# 09_EMMC.net
KiCad netlist of a schematic drawn in Altium Designer
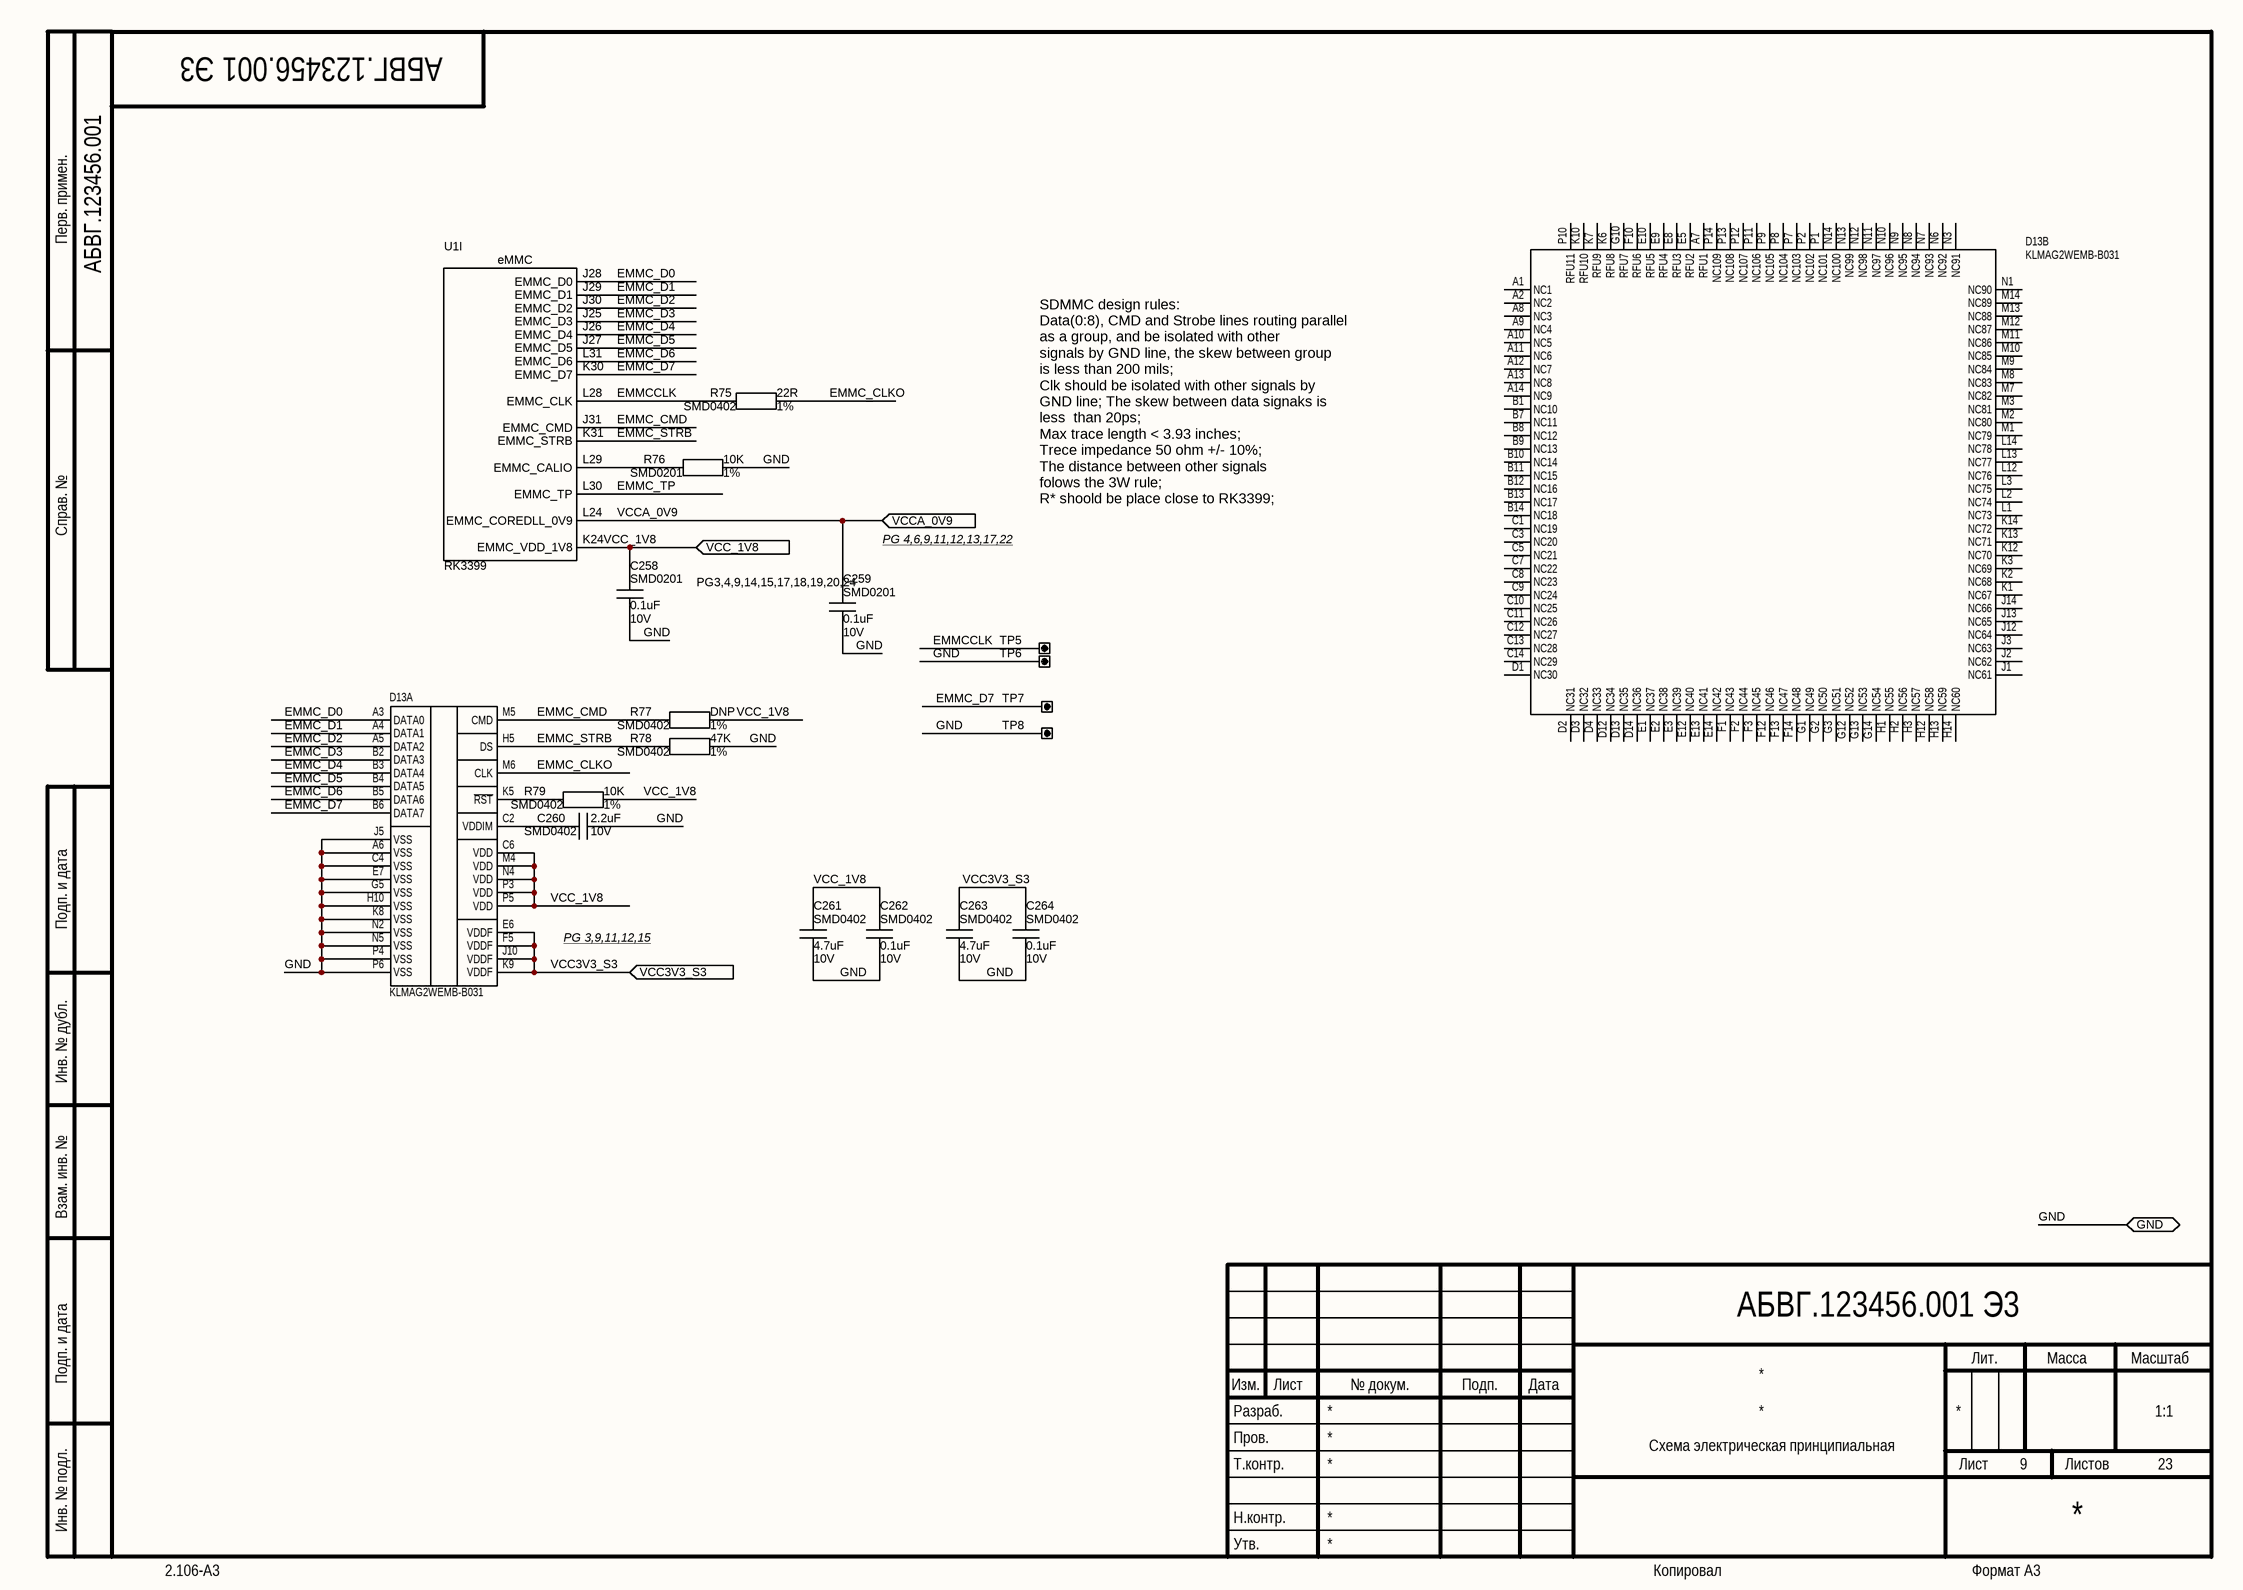
[diagram p0: 09 EMMC.SchDoc]

(export (version "E")
  (design (tool "Eeschema 10.0.6"))
  (components
    (comp (ref "C258")
      (value "0.1uF")
      (footprint "Didur_PcbLib_1:CAP_SMD_0201")
      (fields
        (field (name "PACKAGE") "SMD0201")
        (field (name "PARTNUMBER") "CC0201KRX5R6BB104")
        (field (name "VOLTAGE") "10V")
      )
      (libsource (lib "Didur_SchLib_1") (part "Ceramic_Cap"))
    )
    (comp (ref "C259")
      (value "0.1uF")
      (footprint "Didur_PcbLib_1:CAP_SMD_0201")
      (fields
        (field (name "PACKAGE") "SMD0201")
        (field (name "PARTNUMBER") "CC0201KRX5R6BB104")
        (field (name "VOLTAGE") "10V")
      )
      (libsource (lib "Didur_SchLib_1") (part "Ceramic_Cap"))
    )
    (comp (ref "C260")
      (value "2.2uF")
      (footprint "Didur_PcbLib_1:CAP_SMD_0402")
      (fields
        (field (name "PACKAGE") "SMD0402")
        (field (name "PARTNUMBER") "CC0402KRX5R6BB225")
        (field (name "VOLTAGE") "10V")
      )
      (libsource (lib "Didur_SchLib_1") (part "Ceramic_Cap"))
    )
    (comp (ref "C261")
      (value "4.7uF")
      (footprint "Didur_PcbLib_1:CAP_SMD_0402")
      (fields
        (field (name "PACKAGE") "SMD0402")
        (field (name "PARTNUMBER") "CL05A475KP5NRNC")
        (field (name "VOLTAGE") "10V")
      )
      (libsource (lib "Didur_SchLib_1") (part "Ceramic_Cap"))
    )
    (comp (ref "C262")
      (value "0.1uF")
      (footprint "Didur_PcbLib_1:CAP_SMD_0402")
      (fields
        (field (name "PACKAGE") "SMD0402")
        (field (name "PARTNUMBER") "CC0402KRX5R6BB104")
        (field (name "VOLTAGE") "10V")
      )
      (libsource (lib "Didur_SchLib_1") (part "Ceramic_Cap"))
    )
    (comp (ref "C263")
      (value "4.7uF")
      (footprint "Didur_PcbLib_1:CAP_SMD_0402")
      (fields
        (field (name "PACKAGE") "SMD0402")
        (field (name "PARTNUMBER") "CL05A475KP5NRNC")
        (field (name "VOLTAGE") "10V")
      )
      (libsource (lib "Didur_SchLib_1") (part "Ceramic_Cap"))
    )
    (comp (ref "C264")
      (value "0.1uF")
      (footprint "Didur_PcbLib_1:CAP_SMD_0402")
      (fields
        (field (name "PACKAGE") "SMD0402")
        (field (name "PARTNUMBER") "CC0402KRX5R6BB104")
        (field (name "VOLTAGE") "10V")
      )
      (libsource (lib "Didur_SchLib_1") (part "Ceramic_Cap"))
    )
    (comp (ref "D13")
      (value "KLMAG2WEMB-B031")
      (footprint "Didur_PcbLib_1:FBGA153")
      (libsource (lib "Didur_SchLib_1") (part "KLMAG2WEMB-B031"))
    )
    (comp (ref "R75")
      (value "22R")
      (footprint "Didur_PcbLib_1:RES_SMD_0402_SMALL")
      (fields
        (field (name "PACKAGE") "SMD0402")
        (field (name "PARTNUMBER") "RC0402FR-0722RL")
        (field (name "TOLERANCE") "1%")
      )
      (libsource (lib "") (part "Chip_Res_1"))
    )
    (comp (ref "R76")
      (value "10K")
      (footprint "Didur_PcbLib_1:RES_SMD_0201")
      (fields
        (field (name "PACKAGE") "SMD0201")
        (field (name "PARTNUMBER") "RC0201FR-0710KL")
        (field (name "TOLERANCE") "1%")
      )
      (libsource (lib "Didur_SchLib_1") (part "Chip_Res"))
    )
    (comp (ref "R77")
      (value "DNP")
      (footprint "Didur_PcbLib_1:RES_SMD_0402")
      (fields
        (field (name "PACKAGE") "SMD0402")
        (field (name "PARTNUMBER") "Do Not Place")
        (field (name "TOLERANCE") "1%")
      )
      (libsource (lib "") (part "Chip_Res_2"))
    )
    (comp (ref "R78")
      (value "47K")
      (footprint "Didur_PcbLib_1:RES_SMD_0402")
      (fields
        (field (name "PACKAGE") "SMD0402")
        (field (name "PARTNUMBER") "RC0402FR-1347KL")
        (field (name "TOLERANCE") "1%")
      )
      (libsource (lib "") (part "Chip_Res_1"))
    )
    (comp (ref "R79")
      (value "10K")
      (footprint "Didur_PcbLib_1:RES_SMD_0402")
      (fields
        (field (name "PACKAGE") "SMD0402")
        (field (name "PARTNUMBER") "RC0402FR-0710KL")
        (field (name "TOLERANCE") "1%")
      )
      (libsource (lib "Didur_SchLib_1") (part "Chip_Res"))
    )
    (comp (ref "TP5")
      (value "TEST POINT SMD 1MM")
      (footprint "Didur_PcbLib_1:TEST POINT SMD 1MM")
      (libsource (lib "Didur_SchLib_1") (part "TP"))
    )
    (comp (ref "TP6")
      (value "TEST POINT SMD 1MM")
      (footprint "Didur_PcbLib_1:TEST POINT SMD 1MM")
      (libsource (lib "Didur_SchLib_1") (part "TP"))
    )
    (comp (ref "TP7")
      (value "TEST POINT SMD 1MM")
      (footprint "Didur_PcbLib_1:TEST POINT SMD 1MM")
      (libsource (lib "Didur_SchLib_1") (part "TP"))
    )
    (comp (ref "TP8")
      (value "TEST POINT SMD 1MM")
      (footprint "Didur_PcbLib_1:TEST POINT SMD 1MM")
      (libsource (lib "Didur_SchLib_1") (part "TP"))
    )
    (comp (ref "U1")
      (value "RK3399")
      (footprint "BGA828C65P31X31_2100X2100X161N")
      (fields (field (name "Comment") "RK3399_FF"))
      (libsource (lib "Didur_SchLib_1") (part "RK3399_FF"))
    )
  )
  (nets
    (net (code "1") (name "/EMMCCLK") (class "Default")
      (node (ref "R75") (pin "2") (pinfunction "2_2") (pintype "passive"))
      (node (ref "TP5") (pin "1") (pinfunction "1_1") (pintype "passive"))
      (node (ref "U1") (pin "L28") (pinfunction "EMMC_CLK_L28") (pintype "passive"))
    )
    (net (code "2") (name "/EMMC_CLKO") (class "Default")
      (node (ref "D13") (pin "M6") (pinfunction "CLK_M6") (pintype "passive"))
      (node (ref "R75") (pin "1") (pinfunction "1_1") (pintype "passive"))
    )
    (net (code "3") (name "/EMMC_CMD") (class "Default")
      (node (ref "D13") (pin "M5") (pinfunction "CMD_M5") (pintype "passive"))
      (node (ref "R77") (pin "1") (pinfunction "1_1") (pintype "passive"))
      (node (ref "U1") (pin "J31") (pinfunction "EMMC_CMD_J31") (pintype "passive"))
    )
    (net (code "4") (name "/EMMC_D0") (class "Default")
      (node (ref "D13") (pin "A3") (pinfunction "DATA0_A3") (pintype "passive"))
      (node (ref "U1") (pin "J28") (pinfunction "EMMC_D0_J28") (pintype "passive"))
    )
    (net (code "5") (name "/EMMC_D1") (class "Default")
      (node (ref "D13") (pin "A4") (pinfunction "DATA1_A4") (pintype "passive"))
      (node (ref "U1") (pin "J29") (pinfunction "EMMC_D1_J29") (pintype "passive"))
    )
    (net (code "6") (name "/EMMC_D2") (class "Default")
      (node (ref "D13") (pin "A5") (pinfunction "DATA2_A5") (pintype "passive"))
      (node (ref "U1") (pin "J30") (pinfunction "EMMC_D2_J30") (pintype "passive"))
    )
    (net (code "7") (name "/EMMC_D3") (class "Default")
      (node (ref "D13") (pin "B2") (pinfunction "DATA3_B2") (pintype "passive"))
      (node (ref "U1") (pin "J25") (pinfunction "EMMC_D3_J25") (pintype "passive"))
    )
    (net (code "8") (name "/EMMC_D4") (class "Default")
      (node (ref "D13") (pin "B3") (pinfunction "DATA4_B3") (pintype "passive"))
      (node (ref "U1") (pin "J26") (pinfunction "EMMC_D4_J26") (pintype "passive"))
    )
    (net (code "9") (name "/EMMC_D5") (class "Default")
      (node (ref "D13") (pin "B4") (pinfunction "DATA5_B4") (pintype "passive"))
      (node (ref "U1") (pin "J27") (pinfunction "EMMC_D5_J27") (pintype "passive"))
    )
    (net (code "10") (name "/EMMC_D6") (class "Default")
      (node (ref "D13") (pin "B5") (pinfunction "DATA6_B5") (pintype "passive"))
      (node (ref "U1") (pin "L31") (pinfunction "EMMC_D6_L31") (pintype "passive"))
    )
    (net (code "11") (name "/EMMC_D7") (class "Default")
      (node (ref "D13") (pin "B6") (pinfunction "DATA7_B6") (pintype "passive"))
      (node (ref "TP7") (pin "1") (pinfunction "1_1") (pintype "passive"))
      (node (ref "U1") (pin "K30") (pinfunction "EMMC_D7_K30") (pintype "passive"))
    )
    (net (code "12") (name "/EMMC_STRB") (class "Default")
      (node (ref "D13") (pin "H5") (pinfunction "DS_H5") (pintype "passive"))
      (node (ref "R78") (pin "2") (pinfunction "2_2") (pintype "passive"))
      (node (ref "U1") (pin "K31") (pinfunction "EMMC_STRB_K31") (pintype "passive"))
    )
    (net (code "13") (name "/EMMC_TP") (class "Default")
      (node (ref "U1") (pin "L30") (pinfunction "EMMC_TP_L30") (pintype "passive"))
    )
    (net (code "14") (name "/GND") (class "Default")
      (node (ref "C258") (pin "2") (pinfunction "2_2") (pintype "power_in"))
      (node (ref "C259") (pin "2") (pinfunction "2_2") (pintype "power_in"))
      (node (ref "C260") (pin "2") (pinfunction "2_2") (pintype "power_in"))
      (node (ref "C261") (pin "1") (pinfunction "1_1") (pintype "power_in"))
      (node (ref "C262") (pin "2") (pinfunction "2_2") (pintype "power_in"))
      (node (ref "C263") (pin "1") (pinfunction "1_1") (pintype "power_in"))
      (node (ref "C264") (pin "2") (pinfunction "2_2") (pintype "power_in"))
      (node (ref "D13") (pin "A6") (pinfunction "VSS_A6") (pintype "passive"))
      (node (ref "D13") (pin "C4") (pinfunction "VSS_C4") (pintype "passive"))
      (node (ref "D13") (pin "E7") (pinfunction "VSS_E7") (pintype "passive"))
      (node (ref "D13") (pin "G5") (pinfunction "VSS_G5") (pintype "passive"))
      (node (ref "D13") (pin "H10") (pinfunction "VSS_H10") (pintype "passive"))
      (node (ref "D13") (pin "J5") (pinfunction "VSS_J5") (pintype "passive"))
      (node (ref "D13") (pin "K8") (pinfunction "VSS_K8") (pintype "passive"))
      (node (ref "D13") (pin "N2") (pinfunction "VSS_N2") (pintype "passive"))
      (node (ref "D13") (pin "N5") (pinfunction "VSS_N5") (pintype "passive"))
      (node (ref "D13") (pin "P4") (pinfunction "VSS_P4") (pintype "passive"))
      (node (ref "D13") (pin "P6") (pinfunction "VSS_P6") (pintype "passive"))
      (node (ref "R76") (pin "1") (pinfunction "1_1") (pintype "passive"))
      (node (ref "R78") (pin "1") (pinfunction "1_1") (pintype "passive"))
      (node (ref "TP6") (pin "1") (pinfunction "1_1") (pintype "passive"))
      (node (ref "TP8") (pin "1") (pinfunction "1_1") (pintype "passive"))
    )
    (net (code "15") (name "/VCC3V3_S3") (class "Default")
      (node (ref "C263") (pin "2") (pinfunction "2_2") (pintype "power_in"))
      (node (ref "C264") (pin "1") (pinfunction "1_1") (pintype "power_in"))
      (node (ref "D13") (pin "E6") (pinfunction "VDDF_E6") (pintype "passive"))
      (node (ref "D13") (pin "F5") (pinfunction "VDDF_F5") (pintype "passive"))
      (node (ref "D13") (pin "J10") (pinfunction "VDDF_J10") (pintype "passive"))
      (node (ref "D13") (pin "K9") (pinfunction "VDDF_K9") (pintype "passive"))
    )
    (net (code "16") (name "/VCCA_0V9") (class "Default")
      (node (ref "C259") (pin "1") (pinfunction "1_1") (pintype "power_in"))
      (node (ref "U1") (pin "L24") (pinfunction "EMMC_COREDLL_0V9_L24") (pintype "passive"))
    )
    (net (code "17") (name "/VCC_1V8") (class "Default")
      (node (ref "C258") (pin "1") (pinfunction "1_1") (pintype "power_in"))
      (node (ref "C261") (pin "2") (pinfunction "2_2") (pintype "power_in"))
      (node (ref "C262") (pin "1") (pinfunction "1_1") (pintype "power_in"))
      (node (ref "D13") (pin "C6") (pinfunction "VDD_C6") (pintype "passive"))
      (node (ref "D13") (pin "M4") (pinfunction "VDD_M4") (pintype "passive"))
      (node (ref "D13") (pin "N4") (pinfunction "VDD_N4") (pintype "passive"))
      (node (ref "D13") (pin "P3") (pinfunction "VDD_P3") (pintype "passive"))
      (node (ref "D13") (pin "P5") (pinfunction "VDD_P5") (pintype "passive"))
      (node (ref "R77") (pin "2") (pinfunction "2_2") (pintype "passive"))
      (node (ref "R79") (pin "1") (pinfunction "1_1") (pintype "passive"))
      (node (ref "U1") (pin "K24") (pinfunction "EMMC_VDD_1V8_K24") (pintype "passive"))
    )
    (net (code "18") (name "Net-(D13A-VDDIM)") (class "Default")
      (node (ref "C260") (pin "1") (pinfunction "1_1") (pintype "power_in"))
      (node (ref "D13") (pin "C2") (pinfunction "VDDIM_C2") (pintype "passive"))
    )
    (net (code "19") (name "Net-(D13A-~{RST})") (class "Default")
      (node (ref "D13") (pin "K5") (pinfunction "~{RST}_K5") (pintype "passive"))
      (node (ref "R79") (pin "2") (pinfunction "2_2") (pintype "passive"))
    )
    (net (code "20") (name "Net-(U1I-EMMC_CALIO)") (class "Default")
      (node (ref "R76") (pin "2") (pinfunction "2_2") (pintype "passive"))
      (node (ref "U1") (pin "L29") (pinfunction "EMMC_CALIO_L29") (pintype "passive"))
    )
    (net (code "21") (name "unconnected-(D13B-NC1-PadA1)") (class "Default")
      (node (ref "D13") (pin "A1") (pinfunction "NC1_A1") (pintype "passive"))
    )
    (net (code "22") (name "unconnected-(D13B-NC2-PadA2)") (class "Default")
      (node (ref "D13") (pin "A2") (pinfunction "NC2_A2") (pintype "passive"))
    )
    (net (code "23") (name "unconnected-(D13B-NC3-PadA8)") (class "Default")
      (node (ref "D13") (pin "A8") (pinfunction "NC3_A8") (pintype "passive"))
    )
    (net (code "24") (name "unconnected-(D13B-NC4-PadA9)") (class "Default")
      (node (ref "D13") (pin "A9") (pinfunction "NC4_A9") (pintype "passive"))
    )
    (net (code "25") (name "unconnected-(D13B-NC5-PadA10)") (class "Default")
      (node (ref "D13") (pin "A10") (pinfunction "NC5_A10") (pintype "passive"))
    )
    (net (code "26") (name "unconnected-(D13B-NC6-PadA11)") (class "Default")
      (node (ref "D13") (pin "A11") (pinfunction "NC6_A11") (pintype "passive"))
    )
    (net (code "27") (name "unconnected-(D13B-NC7-PadA12)") (class "Default")
      (node (ref "D13") (pin "A12") (pinfunction "NC7_A12") (pintype "passive"))
    )
    (net (code "28") (name "unconnected-(D13B-NC8-PadA13)") (class "Default")
      (node (ref "D13") (pin "A13") (pinfunction "NC8_A13") (pintype "passive"))
    )
    (net (code "29") (name "unconnected-(D13B-NC9-PadA14)") (class "Default")
      (node (ref "D13") (pin "A14") (pinfunction "NC9_A14") (pintype "passive"))
    )
    (net (code "30") (name "unconnected-(D13B-NC10-PadB1)") (class "Default")
      (node (ref "D13") (pin "B1") (pinfunction "NC10_B1") (pintype "passive"))
    )
    (net (code "31") (name "unconnected-(D13B-NC11-PadB7)") (class "Default")
      (node (ref "D13") (pin "B7") (pinfunction "NC11_B7") (pintype "passive"))
    )
    (net (code "32") (name "unconnected-(D13B-NC12-PadB8)") (class "Default")
      (node (ref "D13") (pin "B8") (pinfunction "NC12_B8") (pintype "passive"))
    )
    (net (code "33") (name "unconnected-(D13B-NC13-PadB9)") (class "Default")
      (node (ref "D13") (pin "B9") (pinfunction "NC13_B9") (pintype "passive"))
    )
    (net (code "34") (name "unconnected-(D13B-NC14-PadB10)") (class "Default")
      (node (ref "D13") (pin "B10") (pinfunction "NC14_B10") (pintype "passive"))
    )
    (net (code "35") (name "unconnected-(D13B-NC15-PadB11)") (class "Default")
      (node (ref "D13") (pin "B11") (pinfunction "NC15_B11") (pintype "passive"))
    )
    (net (code "36") (name "unconnected-(D13B-NC16-PadB12)") (class "Default")
      (node (ref "D13") (pin "B12") (pinfunction "NC16_B12") (pintype "passive"))
    )
    (net (code "37") (name "unconnected-(D13B-NC17-PadB13)") (class "Default")
      (node (ref "D13") (pin "B13") (pinfunction "NC17_B13") (pintype "passive"))
    )
    (net (code "38") (name "unconnected-(D13B-NC18-PadB14)") (class "Default")
      (node (ref "D13") (pin "B14") (pinfunction "NC18_B14") (pintype "passive"))
    )
    (net (code "39") (name "unconnected-(D13B-NC19-PadC1)") (class "Default")
      (node (ref "D13") (pin "C1") (pinfunction "NC19_C1") (pintype "passive"))
    )
    (net (code "40") (name "unconnected-(D13B-NC20-PadC3)") (class "Default")
      (node (ref "D13") (pin "C3") (pinfunction "NC20_C3") (pintype "passive"))
    )
    (net (code "41") (name "unconnected-(D13B-NC21-PadC5)") (class "Default")
      (node (ref "D13") (pin "C5") (pinfunction "NC21_C5") (pintype "passive"))
    )
    (net (code "42") (name "unconnected-(D13B-NC22-PadC7)") (class "Default")
      (node (ref "D13") (pin "C7") (pinfunction "NC22_C7") (pintype "passive"))
    )
    (net (code "43") (name "unconnected-(D13B-NC23-PadC8)") (class "Default")
      (node (ref "D13") (pin "C8") (pinfunction "NC23_C8") (pintype "passive"))
    )
    (net (code "44") (name "unconnected-(D13B-NC24-PadC9)") (class "Default")
      (node (ref "D13") (pin "C9") (pinfunction "NC24_C9") (pintype "passive"))
    )
    (net (code "45") (name "unconnected-(D13B-NC25-PadC10)") (class "Default")
      (node (ref "D13") (pin "C10") (pinfunction "NC25_C10") (pintype "passive"))
    )
    (net (code "46") (name "unconnected-(D13B-NC26-PadC11)") (class "Default")
      (node (ref "D13") (pin "C11") (pinfunction "NC26_C11") (pintype "passive"))
    )
    (net (code "47") (name "unconnected-(D13B-NC27-PadC12)") (class "Default")
      (node (ref "D13") (pin "C12") (pinfunction "NC27_C12") (pintype "passive"))
    )
    (net (code "48") (name "unconnected-(D13B-NC28-PadC13)") (class "Default")
      (node (ref "D13") (pin "C13") (pinfunction "NC28_C13") (pintype "passive"))
    )
    (net (code "49") (name "unconnected-(D13B-NC29-PadC14)") (class "Default")
      (node (ref "D13") (pin "C14") (pinfunction "NC29_C14") (pintype "passive"))
    )
    (net (code "50") (name "unconnected-(D13B-NC30-PadD1)") (class "Default")
      (node (ref "D13") (pin "D1") (pinfunction "NC30_D1") (pintype "passive"))
    )
    (net (code "51") (name "unconnected-(D13B-NC31-PadD2)") (class "Default")
      (node (ref "D13") (pin "D2") (pinfunction "NC31_D2") (pintype "passive"))
    )
    (net (code "52") (name "unconnected-(D13B-NC32-PadD3)") (class "Default")
      (node (ref "D13") (pin "D3") (pinfunction "NC32_D3") (pintype "passive"))
    )
    (net (code "53") (name "unconnected-(D13B-NC33-PadD4)") (class "Default")
      (node (ref "D13") (pin "D4") (pinfunction "NC33_D4") (pintype "passive"))
    )
    (net (code "54") (name "unconnected-(D13B-NC34-PadD12)") (class "Default")
      (node (ref "D13") (pin "D12") (pinfunction "NC34_D12") (pintype "passive"))
    )
    (net (code "55") (name "unconnected-(D13B-NC35-PadD13)") (class "Default")
      (node (ref "D13") (pin "D13") (pinfunction "NC35_D13") (pintype "passive"))
    )
    (net (code "56") (name "unconnected-(D13B-NC36-PadD14)") (class "Default")
      (node (ref "D13") (pin "D14") (pinfunction "NC36_D14") (pintype "passive"))
    )
    (net (code "57") (name "unconnected-(D13B-NC37-PadE1)") (class "Default")
      (node (ref "D13") (pin "E1") (pinfunction "NC37_E1") (pintype "passive"))
    )
    (net (code "58") (name "unconnected-(D13B-NC38-PadE2)") (class "Default")
      (node (ref "D13") (pin "E2") (pinfunction "NC38_E2") (pintype "passive"))
    )
    (net (code "59") (name "unconnected-(D13B-NC39-PadE3)") (class "Default")
      (node (ref "D13") (pin "E3") (pinfunction "NC39_E3") (pintype "passive"))
    )
    (net (code "60") (name "unconnected-(D13B-NC40-PadE12)") (class "Default")
      (node (ref "D13") (pin "E12") (pinfunction "NC40_E12") (pintype "passive"))
    )
    (net (code "61") (name "unconnected-(D13B-NC41-PadE13)") (class "Default")
      (node (ref "D13") (pin "E13") (pinfunction "NC41_E13") (pintype "passive"))
    )
    (net (code "62") (name "unconnected-(D13B-NC42-PadE14)") (class "Default")
      (node (ref "D13") (pin "E14") (pinfunction "NC42_E14") (pintype "passive"))
    )
    (net (code "63") (name "unconnected-(D13B-NC43-PadF1)") (class "Default")
      (node (ref "D13") (pin "F1") (pinfunction "NC43_F1") (pintype "passive"))
    )
    (net (code "64") (name "unconnected-(D13B-NC44-PadF2)") (class "Default")
      (node (ref "D13") (pin "F2") (pinfunction "NC44_F2") (pintype "passive"))
    )
    (net (code "65") (name "unconnected-(D13B-NC45-PadF3)") (class "Default")
      (node (ref "D13") (pin "F3") (pinfunction "NC45_F3") (pintype "passive"))
    )
    (net (code "66") (name "unconnected-(D13B-NC46-PadF12)") (class "Default")
      (node (ref "D13") (pin "F12") (pinfunction "NC46_F12") (pintype "passive"))
    )
    (net (code "67") (name "unconnected-(D13B-NC47-PadF13)") (class "Default")
      (node (ref "D13") (pin "F13") (pinfunction "NC47_F13") (pintype "passive"))
    )
    (net (code "68") (name "unconnected-(D13B-NC48-PadF14)") (class "Default")
      (node (ref "D13") (pin "F14") (pinfunction "NC48_F14") (pintype "passive"))
    )
    (net (code "69") (name "unconnected-(D13B-NC49-PadG1)") (class "Default")
      (node (ref "D13") (pin "G1") (pinfunction "NC49_G1") (pintype "passive"))
    )
    (net (code "70") (name "unconnected-(D13B-NC50-PadG2)") (class "Default")
      (node (ref "D13") (pin "G2") (pinfunction "NC50_G2") (pintype "passive"))
    )
    (net (code "71") (name "unconnected-(D13B-NC51-PadG3)") (class "Default")
      (node (ref "D13") (pin "G3") (pinfunction "NC51_G3") (pintype "passive"))
    )
    (net (code "72") (name "unconnected-(D13B-NC52-PadG12)") (class "Default")
      (node (ref "D13") (pin "G12") (pinfunction "NC52_G12") (pintype "passive"))
    )
    (net (code "73") (name "unconnected-(D13B-NC53-PadG13)") (class "Default")
      (node (ref "D13") (pin "G13") (pinfunction "NC53_G13") (pintype "passive"))
    )
    (net (code "74") (name "unconnected-(D13B-NC54-PadG14)") (class "Default")
      (node (ref "D13") (pin "G14") (pinfunction "NC54_G14") (pintype "passive"))
    )
    (net (code "75") (name "unconnected-(D13B-NC55-PadH1)") (class "Default")
      (node (ref "D13") (pin "H1") (pinfunction "NC55_H1") (pintype "passive"))
    )
    (net (code "76") (name "unconnected-(D13B-NC56-PadH2)") (class "Default")
      (node (ref "D13") (pin "H2") (pinfunction "NC56_H2") (pintype "passive"))
    )
    (net (code "77") (name "unconnected-(D13B-NC57-PadH3)") (class "Default")
      (node (ref "D13") (pin "H3") (pinfunction "NC57_H3") (pintype "passive"))
    )
    (net (code "78") (name "unconnected-(D13B-NC58-PadH12)") (class "Default")
      (node (ref "D13") (pin "H12") (pinfunction "NC58_H12") (pintype "passive"))
    )
    (net (code "79") (name "unconnected-(D13B-NC59-PadH13)") (class "Default")
      (node (ref "D13") (pin "H13") (pinfunction "NC59_H13") (pintype "passive"))
    )
    (net (code "80") (name "unconnected-(D13B-NC60-PadH14)") (class "Default")
      (node (ref "D13") (pin "H14") (pinfunction "NC60_H14") (pintype "passive"))
    )
    (net (code "81") (name "unconnected-(D13B-NC61-PadJ1)") (class "Default")
      (node (ref "D13") (pin "J1") (pinfunction "NC61_J1") (pintype "passive"))
    )
    (net (code "82") (name "unconnected-(D13B-NC62-PadJ2)") (class "Default")
      (node (ref "D13") (pin "J2") (pinfunction "NC62_J2") (pintype "passive"))
    )
    (net (code "83") (name "unconnected-(D13B-NC63-PadJ3)") (class "Default")
      (node (ref "D13") (pin "J3") (pinfunction "NC63_J3") (pintype "passive"))
    )
    (net (code "84") (name "unconnected-(D13B-NC64-PadJ12)") (class "Default")
      (node (ref "D13") (pin "J12") (pinfunction "NC64_J12") (pintype "passive"))
    )
    (net (code "85") (name "unconnected-(D13B-NC65-PadJ13)") (class "Default")
      (node (ref "D13") (pin "J13") (pinfunction "NC65_J13") (pintype "passive"))
    )
    (net (code "86") (name "unconnected-(D13B-NC66-PadJ14)") (class "Default")
      (node (ref "D13") (pin "J14") (pinfunction "NC66_J14") (pintype "passive"))
    )
    (net (code "87") (name "unconnected-(D13B-NC67-PadK1)") (class "Default")
      (node (ref "D13") (pin "K1") (pinfunction "NC67_K1") (pintype "passive"))
    )
    (net (code "88") (name "unconnected-(D13B-NC68-PadK2)") (class "Default")
      (node (ref "D13") (pin "K2") (pinfunction "NC68_K2") (pintype "passive"))
    )
    (net (code "89") (name "unconnected-(D13B-NC69-PadK3)") (class "Default")
      (node (ref "D13") (pin "K3") (pinfunction "NC69_K3") (pintype "passive"))
    )
    (net (code "90") (name "unconnected-(D13B-NC70-PadK12)") (class "Default")
      (node (ref "D13") (pin "K12") (pinfunction "NC70_K12") (pintype "passive"))
    )
    (net (code "91") (name "unconnected-(D13B-NC71-PadK13)") (class "Default")
      (node (ref "D13") (pin "K13") (pinfunction "NC71_K13") (pintype "passive"))
    )
    (net (code "92") (name "unconnected-(D13B-NC72-PadK14)") (class "Default")
      (node (ref "D13") (pin "K14") (pinfunction "NC72_K14") (pintype "passive"))
    )
    (net (code "93") (name "unconnected-(D13B-NC73-PadL1)") (class "Default")
      (node (ref "D13") (pin "L1") (pinfunction "NC73_L1") (pintype "passive"))
    )
    (net (code "94") (name "unconnected-(D13B-NC74-PadL2)") (class "Default")
      (node (ref "D13") (pin "L2") (pinfunction "NC74_L2") (pintype "passive"))
    )
    (net (code "95") (name "unconnected-(D13B-NC75-PadL3)") (class "Default")
      (node (ref "D13") (pin "L3") (pinfunction "NC75_L3") (pintype "passive"))
    )
    (net (code "96") (name "unconnected-(D13B-NC76-PadL12)") (class "Default")
      (node (ref "D13") (pin "L12") (pinfunction "NC76_L12") (pintype "passive"))
    )
    (net (code "97") (name "unconnected-(D13B-NC77-PadL13)") (class "Default")
      (node (ref "D13") (pin "L13") (pinfunction "NC77_L13") (pintype "passive"))
    )
    (net (code "98") (name "unconnected-(D13B-NC78-PadL14)") (class "Default")
      (node (ref "D13") (pin "L14") (pinfunction "NC78_L14") (pintype "passive"))
    )
    (net (code "99") (name "unconnected-(D13B-NC79-PadM1)") (class "Default")
      (node (ref "D13") (pin "M1") (pinfunction "NC79_M1") (pintype "passive"))
    )
    (net (code "100") (name "unconnected-(D13B-NC80-PadM2)") (class "Default")
      (node (ref "D13") (pin "M2") (pinfunction "NC80_M2") (pintype "passive"))
    )
    (net (code "101") (name "unconnected-(D13B-NC81-PadM3)") (class "Default")
      (node (ref "D13") (pin "M3") (pinfunction "NC81_M3") (pintype "passive"))
    )
    (net (code "102") (name "unconnected-(D13B-NC82-PadM7)") (class "Default")
      (node (ref "D13") (pin "M7") (pinfunction "NC82_M7") (pintype "passive"))
    )
    (net (code "103") (name "unconnected-(D13B-NC83-PadM8)") (class "Default")
      (node (ref "D13") (pin "M8") (pinfunction "NC83_M8") (pintype "passive"))
    )
    (net (code "104") (name "unconnected-(D13B-NC84-PadM9)") (class "Default")
      (node (ref "D13") (pin "M9") (pinfunction "NC84_M9") (pintype "passive"))
    )
    (net (code "105") (name "unconnected-(D13B-NC85-PadM10)") (class "Default")
      (node (ref "D13") (pin "M10") (pinfunction "NC85_M10") (pintype "passive"))
    )
    (net (code "106") (name "unconnected-(D13B-NC86-PadM11)") (class "Default")
      (node (ref "D13") (pin "M11") (pinfunction "NC86_M11") (pintype "passive"))
    )
    (net (code "107") (name "unconnected-(D13B-NC87-PadM12)") (class "Default")
      (node (ref "D13") (pin "M12") (pinfunction "NC87_M12") (pintype "passive"))
    )
    (net (code "108") (name "unconnected-(D13B-NC88-PadM13)") (class "Default")
      (node (ref "D13") (pin "M13") (pinfunction "NC88_M13") (pintype "passive"))
    )
    (net (code "109") (name "unconnected-(D13B-NC89-PadM14)") (class "Default")
      (node (ref "D13") (pin "M14") (pinfunction "NC89_M14") (pintype "passive"))
    )
    (net (code "110") (name "unconnected-(D13B-NC90-PadN1)") (class "Default")
      (node (ref "D13") (pin "N1") (pinfunction "NC90_N1") (pintype "passive"))
    )
    (net (code "111") (name "unconnected-(D13B-NC91-PadN3)") (class "Default")
      (node (ref "D13") (pin "N3") (pinfunction "NC91_N3") (pintype "passive"))
    )
    (net (code "112") (name "unconnected-(D13B-NC92-PadN6)") (class "Default")
      (node (ref "D13") (pin "N6") (pinfunction "NC92_N6") (pintype "passive"))
    )
    (net (code "113") (name "unconnected-(D13B-NC93-PadN7)") (class "Default")
      (node (ref "D13") (pin "N7") (pinfunction "NC93_N7") (pintype "passive"))
    )
    (net (code "114") (name "unconnected-(D13B-NC94-PadN8)") (class "Default")
      (node (ref "D13") (pin "N8") (pinfunction "NC94_N8") (pintype "passive"))
    )
    (net (code "115") (name "unconnected-(D13B-NC95-PadN9)") (class "Default")
      (node (ref "D13") (pin "N9") (pinfunction "NC95_N9") (pintype "passive"))
    )
    (net (code "116") (name "unconnected-(D13B-NC96-PadN10)") (class "Default")
      (node (ref "D13") (pin "N10") (pinfunction "NC96_N10") (pintype "passive"))
    )
    (net (code "117") (name "unconnected-(D13B-NC97-PadN11)") (class "Default")
      (node (ref "D13") (pin "N11") (pinfunction "NC97_N11") (pintype "passive"))
    )
    (net (code "118") (name "unconnected-(D13B-NC98-PadN12)") (class "Default")
      (node (ref "D13") (pin "N12") (pinfunction "NC98_N12") (pintype "passive"))
    )
    (net (code "119") (name "unconnected-(D13B-NC99-PadN13)") (class "Default")
      (node (ref "D13") (pin "N13") (pinfunction "NC99_N13") (pintype "passive"))
    )
    (net (code "120") (name "unconnected-(D13B-NC100-PadN14)") (class "Default")
      (node (ref "D13") (pin "N14") (pinfunction "NC100_N14") (pintype "passive"))
    )
    (net (code "121") (name "unconnected-(D13B-NC101-PadP1)") (class "Default")
      (node (ref "D13") (pin "P1") (pinfunction "NC101_P1") (pintype "passive"))
    )
    (net (code "122") (name "unconnected-(D13B-NC102-PadP2)") (class "Default")
      (node (ref "D13") (pin "P2") (pinfunction "NC102_P2") (pintype "passive"))
    )
    (net (code "123") (name "unconnected-(D13B-NC103-PadP7)") (class "Default")
      (node (ref "D13") (pin "P7") (pinfunction "NC103_P7") (pintype "passive"))
    )
    (net (code "124") (name "unconnected-(D13B-NC104-PadP8)") (class "Default")
      (node (ref "D13") (pin "P8") (pinfunction "NC104_P8") (pintype "passive"))
    )
    (net (code "125") (name "unconnected-(D13B-NC105-PadP9)") (class "Default")
      (node (ref "D13") (pin "P9") (pinfunction "NC105_P9") (pintype "passive"))
    )
    (net (code "126") (name "unconnected-(D13B-NC106-PadP11)") (class "Default")
      (node (ref "D13") (pin "P11") (pinfunction "NC106_P11") (pintype "passive"))
    )
    (net (code "127") (name "unconnected-(D13B-NC107-PadP12)") (class "Default")
      (node (ref "D13") (pin "P12") (pinfunction "NC107_P12") (pintype "passive"))
    )
    (net (code "128") (name "unconnected-(D13B-NC108-PadP13)") (class "Default")
      (node (ref "D13") (pin "P13") (pinfunction "NC108_P13") (pintype "passive"))
    )
    (net (code "129") (name "unconnected-(D13B-NC109-PadP14)") (class "Default")
      (node (ref "D13") (pin "P14") (pinfunction "NC109_P14") (pintype "passive"))
    )
    (net (code "130") (name "unconnected-(D13B-RFU1-PadA7)") (class "Default")
      (node (ref "D13") (pin "A7") (pinfunction "RFU1_A7") (pintype "passive"))
    )
    (net (code "131") (name "unconnected-(D13B-RFU2-PadE5)") (class "Default")
      (node (ref "D13") (pin "E5") (pinfunction "RFU2_E5") (pintype "passive"))
    )
    (net (code "132") (name "unconnected-(D13B-RFU3-PadE8)") (class "Default")
      (node (ref "D13") (pin "E8") (pinfunction "RFU3_E8") (pintype "passive"))
    )
    (net (code "133") (name "unconnected-(D13B-RFU4-PadE9)") (class "Default")
      (node (ref "D13") (pin "E9") (pinfunction "RFU4_E9") (pintype "passive"))
    )
    (net (code "134") (name "unconnected-(D13B-RFU5-PadE10)") (class "Default")
      (node (ref "D13") (pin "E10") (pinfunction "RFU5_E10") (pintype "passive"))
    )
    (net (code "135") (name "unconnected-(D13B-RFU6-PadF10)") (class "Default")
      (node (ref "D13") (pin "F10") (pinfunction "RFU6_F10") (pintype "passive"))
    )
    (net (code "136") (name "unconnected-(D13B-RFU7-PadG10)") (class "Default")
      (node (ref "D13") (pin "G10") (pinfunction "RFU7_G10") (pintype "passive"))
    )
    (net (code "137") (name "unconnected-(D13B-RFU8-PadK6)") (class "Default")
      (node (ref "D13") (pin "K6") (pinfunction "RFU8_K6") (pintype "passive"))
    )
    (net (code "138") (name "unconnected-(D13B-RFU9-PadK7)") (class "Default")
      (node (ref "D13") (pin "K7") (pinfunction "RFU9_K7") (pintype "passive"))
    )
    (net (code "139") (name "unconnected-(D13B-RFU10-PadK10)") (class "Default")
      (node (ref "D13") (pin "K10") (pinfunction "RFU10_K10") (pintype "passive"))
    )
    (net (code "140") (name "unconnected-(D13B-RFU11-PadP10)") (class "Default")
      (node (ref "D13") (pin "P10") (pinfunction "RFU11_P10") (pintype "passive"))
    )
  )
)
